# PCB-DISP-BO.net
KiCad netlist of a schematic drawn in EAGLE
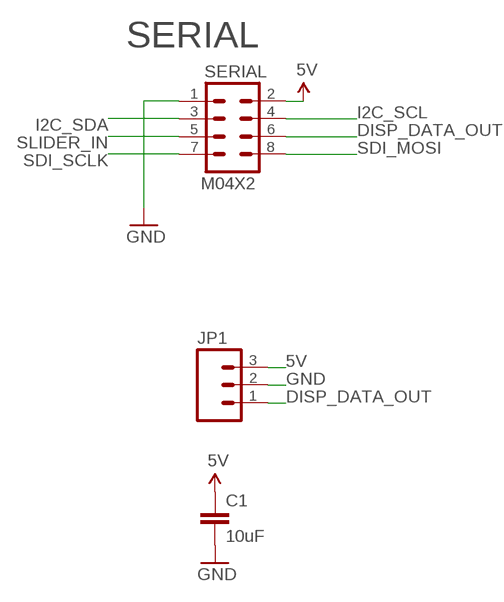
[diagram p0: schematic, sheet 1]

(export (version "E")
  (design (tool "Eeschema 10.0.6"))
  (components
    (comp (ref "C1")
      (value "10uF")
      (footprint "eagle-import:0603-CAP")
      (libsource (lib "eagle-import") (part "CAP0603-CAP"))
    )
    (comp (ref "JP1")
      (value "M03PTH")
      (footprint "eagle-import:1X03")
      (libsource (lib "eagle-import") (part "M03PTH"))
    )
    (comp (ref "SERIAL")
      (value "M04X2")
      (footprint "eagle-import:2X4")
      (libsource (lib "eagle-import") (part "M04X2"))
    )
  )
  (nets
    (net (code "1") (name "/DISP_DATA_OUT") (class "Default")
      (node (ref "JP1") (pin "1") (pinfunction "1_1") (pintype "passive"))
      (node (ref "SERIAL") (pin "6") (pinfunction "6_6") (pintype "passive"))
    )
    (net (code "2") (name "/I2C_SCL") (class "Default")
      (node (ref "SERIAL") (pin "4") (pinfunction "4_4") (pintype "passive"))
    )
    (net (code "3") (name "/I2C_SDA") (class "Default")
      (node (ref "SERIAL") (pin "3") (pinfunction "3_3") (pintype "passive"))
    )
    (net (code "4") (name "/SDI_MOSI") (class "Default")
      (node (ref "SERIAL") (pin "8") (pinfunction "8_8") (pintype "passive"))
    )
    (net (code "5") (name "/SDI_SCLK") (class "Default")
      (node (ref "SERIAL") (pin "7") (pinfunction "7_7") (pintype "passive"))
    )
    (net (code "6") (name "/SLIDER_IN") (class "Default")
      (node (ref "SERIAL") (pin "5") (pinfunction "5_5") (pintype "passive"))
    )
    (net (code "7") (name "5V") (class "Default")
      (node (ref "C1") (pin "1") (pinfunction "1_1") (pintype "passive"))
      (node (ref "JP1") (pin "3") (pinfunction "3_3") (pintype "passive"))
      (node (ref "SERIAL") (pin "2") (pinfunction "2_2") (pintype "passive"))
    )
    (net (code "8") (name "GND") (class "Default")
      (node (ref "C1") (pin "2") (pinfunction "2_2") (pintype "passive"))
      (node (ref "JP1") (pin "2") (pinfunction "2_2") (pintype "passive"))
      (node (ref "SERIAL") (pin "1") (pinfunction "1_1") (pintype "passive"))
    )
  )
)
